# InputISO_Block.net
KiCad netlist of a schematic drawn in Altium Designer
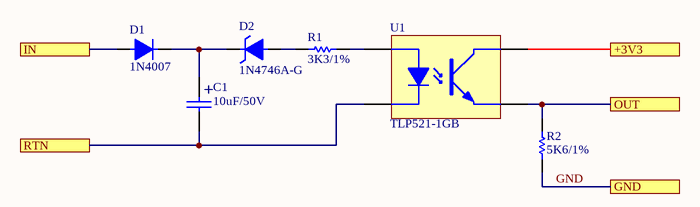
[diagram p0: InputISO_Block.SchDoc]

(export (version "E")
  (design (tool "Eeschema 10.0.6"))
  (components
    (comp (ref "C1")
      (value "10uF/50V")
      (footprint "CAP100RP")
      (fields (field (name "JLCPART") "C2960372"))
      (libsource (lib "LIB2022 - Passives") (part "CAPPOL-THT"))
    )
    (comp (ref "D1")
      (value "1N4007")
      (footprint "DO41")
      (description "Diode Rectifier")
      (fields (field (name "JLCPART") "C3033995"))
      (libsource (lib "LIB2022 - Semiconductors") (part "DIODE RECTIFIER"))
    )
    (comp (ref "D2")
      (value "1N4746A-G")
      (footprint "DO40")
      (description "Diode Zener")
      (fields (field (name "JLCPART") "C391338"))
      (libsource (lib "LIB2022 - Semiconductors") (part "DIODE ZENER"))
    )
    (comp (ref "R1")
      (value "3K3/1%")
      (footprint "RES400")
      (fields (field (name "JLCPART") "C119335"))
      (libsource (lib "LIB2022 - Passives") (part "RES-THT"))
    )
    (comp (ref "R2")
      (value "5K6/1%")
      (footprint "RES400")
      (fields (field (name "JLCPART") "C173035"))
      (libsource (lib "LIB2022 - Passives") (part "RES-THT"))
    )
    (comp (ref "U1")
      (value "TLP521-1GB")
      (footprint "DIP4")
      (fields (field (name "JLCPART") "C69256"))
      (libsource (lib "LIB2022 - ICs") (part "TLP521-1"))
    )
  )
  (nets
    (net (code "1") (name "/+3V3") (class "Default")
      (node (ref "U1") (pin "4") (pinfunction "C_4") (pintype "passive"))
    )
    (net (code "2") (name "/GND") (class "Default")
      (node (ref "R2") (pin "1") (pinfunction "1_1") (pintype "passive"))
    )
    (net (code "3") (name "/IN") (class "Default")
      (node (ref "D1") (pin "1") (pinfunction "1_1") (pintype "passive"))
    )
    (net (code "4") (name "/OUT") (class "Default")
      (node (ref "R2") (pin "2") (pinfunction "2_2") (pintype "passive"))
      (node (ref "U1") (pin "3") (pinfunction "E_3") (pintype "passive"))
    )
    (net (code "5") (name "/RTN") (class "Default")
      (node (ref "C1") (pin "2") (pinfunction "2_2") (pintype "passive"))
      (node (ref "U1") (pin "2") (pinfunction "K_2") (pintype "passive"))
    )
    (net (code "6") (name "Net-(C1-Pad1)") (class "Default")
      (node (ref "C1") (pin "1") (pinfunction "1_1") (pintype "passive"))
      (node (ref "D1") (pin "2") (pinfunction "2_2") (pintype "passive"))
      (node (ref "D2") (pin "2") (pinfunction "2_2") (pintype "passive"))
    )
    (net (code "7") (name "Net-(D2-Pad1)") (class "Default")
      (node (ref "D2") (pin "1") (pinfunction "1_1") (pintype "passive"))
      (node (ref "R1") (pin "1") (pinfunction "1_1") (pintype "passive"))
    )
    (net (code "8") (name "Net-(U1-A)") (class "Default")
      (node (ref "R1") (pin "2") (pinfunction "2_2") (pintype "passive"))
      (node (ref "U1") (pin "1") (pinfunction "A_1") (pintype "passive"))
    )
  )
)
